# HV_BUCK.net
KiCad netlist of a schematic drawn in Altium Designer
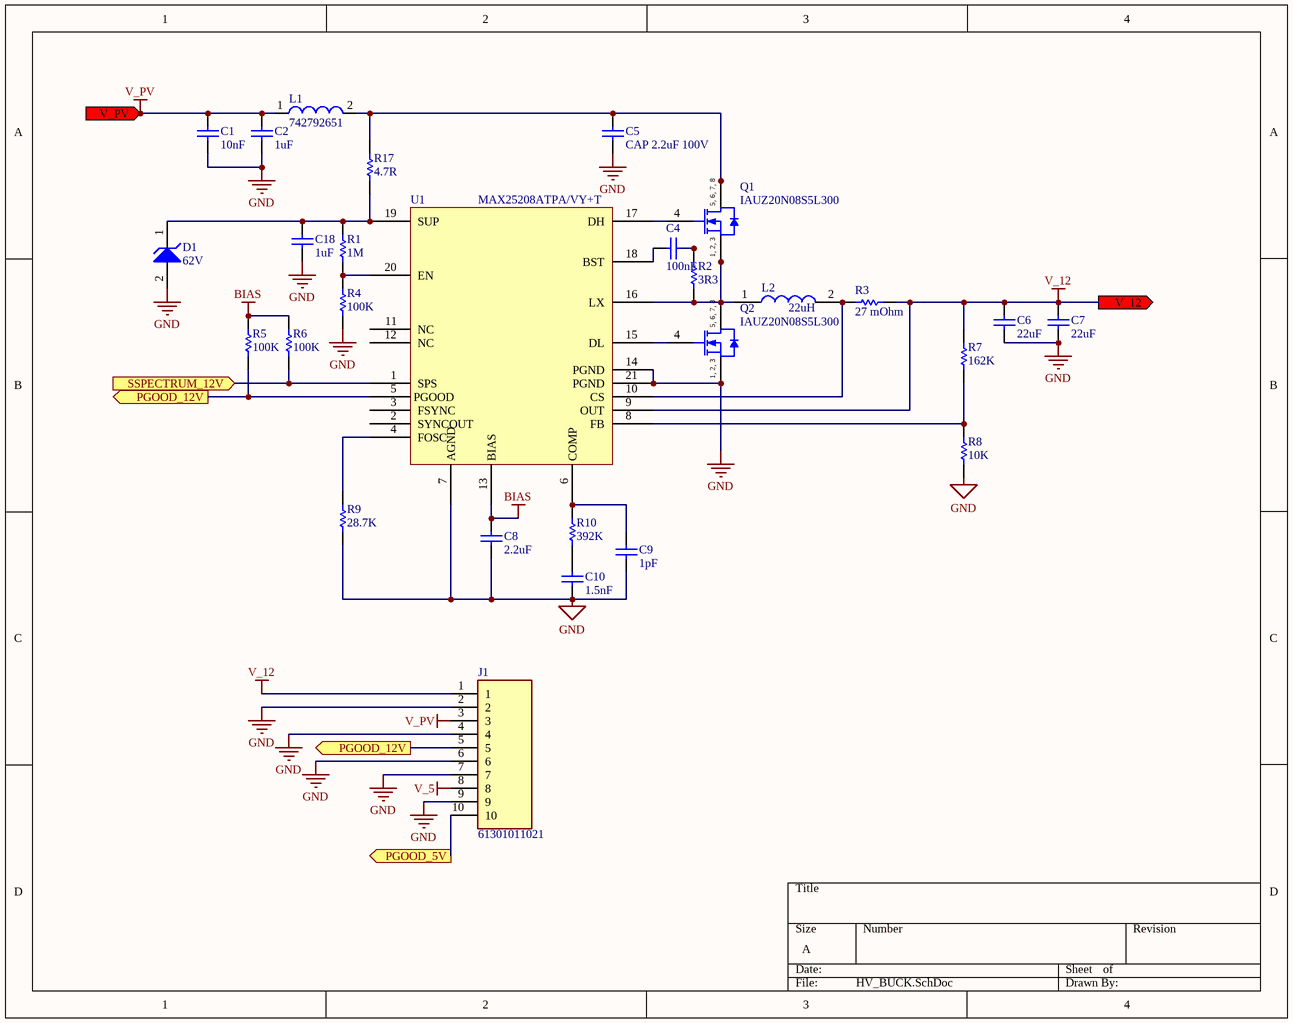
[diagram p0: HV_BUCK.SchDoc]

(export (version "E")
  (design (tool "Eeschema 10.0.6"))
  (components
    (comp (ref "C1")
      (value "10nF")
      (footprint "CAPC2013X94X50ML20T25")
      (description "Cap Ceramic 0.01uF 100V X7R 10% SMD 0805 FlexiTerm 125C Paper T/R")
      (fields
        (field (name "MANUFACTURER") "AVX Interconnect / Elco")
        (field (name "PART NUMBER") "08051C103KAZ2A")
      )
      (libsource (lib "Altium Content Vault") (part "CAP"))
    )
    (comp (ref "C2")
      (value "1uF")
      (footprint "CAPC3216X180X50NL20T25")
      (description "Chip Capacitor, 1 uF, +/- 10%, 100 V, -55 to 125 degC, 1206 (3216 Metric), RoHS, Tape and Reel")
      (fields (field (name "MANUFACTURER") "AVX"))
      (libsource (lib "Altium Content Vault") (part "CAP-NP-2"))
    )
    (comp (ref "C4")
      (value "100nF")
      (footprint "CAPC1005X56X25NL10T15")
      (fields
        (field (name "MANUFACTURER") "AVX Interconnect / Elco")
        (field (name "PART NUMBER") "0402YC104KAT2A")
        (field (name "TOLERANCE") "10%")
      )
      (libsource (lib "Altium Content Vault") (part "CAP"))
    )
    (comp (ref "C5")
      (value "CAP 2.2uF 100V")
      (footprint "CAPC1210(3225)280_N")
      (description "CAP 2.2uF 100V ±10% 1210 (3225 Metric) Thickness 2.8mm SMD")
      (fields (field (name "TOLERANCE") "Â±10%"))
      (libsource (lib "Altium Content Vault") (part "CAP"))
    )
    (comp (ref "C6")
      (value "22uF")
      (footprint "CAPC3225X279X50NL20T25")
      (description "Ceramic Capacitor, 25 V, 22 uF, +/-10%, -55 to 85 degC, 2-Pin SMD (1210), RoHS, Tape and Reel")
      (fields (field (name "TOLERANCE") "10%") (field (name "MANUFACTURER") "AVX"))
      (libsource (lib "Altium Content Vault") (part "CAP-NP-2"))
    )
    (comp (ref "C7")
      (value "22uF")
      (footprint "CAPC3225X279X50NL20T25")
      (description "Ceramic Capacitor, 25 V, 22 uF, +/-10%, -55 to 85 degC, 2-Pin SMD (1210), RoHS, Tape and Reel")
      (fields (field (name "TOLERANCE") "10%") (field (name "MANUFACTURER") "AVX"))
      (libsource (lib "Altium Content Vault") (part "CAP-NP-2"))
    )
    (comp (ref "C8")
      (value "2.2uF")
      (footprint "CAPC2013X135X50ML10T20")
      (fields
        (field (name "MANUFACTURER") "Murata")
        (field (name "PART NUMBER") "GRM21BR71C225KA12L")
        (field (name "TOLERANCE") "10%")
      )
      (libsource (lib "Altium Content Vault") (part "CAP"))
    )
    (comp (ref "C9")
      (value "1pF")
      (footprint "CAPC1005X55X25NL05T05")
      (description "Chip Capacitor, 1 pF, +/- 0.25 pF, 50 V, -55 to 125 degC, 0402 (1005 Metric), RoHS, Tape and Reel")
      (fields (field (name "TOLERANCE") "5%") (field (name "MANUFACTURER") "Yageo"))
      (libsource (lib "Altium Content Vault") (part "CAP-NP-2"))
    )
    (comp (ref "C10")
      (value "1.5nF")
      (footprint "CAPC1005X55X25ML05T10")
      (fields
        (field (name "PART NUMBER") "GRM155R71H152KA01D")
        (field (name "MANUFACTURER") "Murata")
        (field (name "TOLERANCE") "10%")
      )
      (libsource (lib "Altium Content Vault") (part "CAP"))
    )
    (comp (ref "C18")
      (value "1uF")
      (footprint "CAPC2013X145X20NL20")
      (description "Chip Capacitor, 1 uF, +/- 10%, 100 V, -55 to 125 degC, 0805 (2012 Metric), RoHS, Tape and Reel")
      (fields
        (field (name "PCN PART NUMBER") "MLCCPartNumberChange30/Nov/2012")
        (field (name "MANUFACTURER") "TDK")
      )
      (libsource (lib "Altium Content Vault") (part "CAP-NP-2"))
    )
    (comp (ref "D1")
      (value "62V")
      (footprint "ONSC-SOD-123-2-425-04_V")
      (description "Zener Voltage Regulator, 500 mW, 2-Pin SOD-123, Pb-Free, Tape and Reel")
      (fields (field (name "MANUFACTURER") "On Semiconductor") (field (name "PARTNUMBER") "SZMMSZ5265BT1G"))
      (libsource (lib "Altium Content Vault") (part "ONSC-K1A2-2"))
    )
    (comp (ref "J1")
      (value "61301011021")
      (footprint "SamacSys:HDRRA10W64P0X254_1X10_2540X254X254P")
      (description "Connector")
      (fields (field (name "MOUSER PART NUMBER") "710-61301011021"))
      (libsource (lib "*") (part "61301011021"))
    )
    (comp (ref "L1")
      (value "742792651")
      (footprint "SMD-0603")
      (description "SMD EMI Suppression Ferrite Bead WE-CBF, Z = 600 Ohm")
      (fields (field (name "MANUFACTURER") "Wurth Electronics") (field (name "TOLERANCE") "25%"))
      (libsource (lib "Altium Content Vault") (part "PAS-IND-INDUCTOR-2"))
    )
    (comp (ref "L2")
      (value "22uH")
      (footprint "SamacSys:INDPM8680X400N")
      (description "Inductor 22uH")
      (fields
        (field (name "MANUFACTURER_PART_NUMBER") "MPX1D0840L220")
        (field (name "MOUSER PART NUMBER") "80-MPX1D0840L220")
      )
      (libsource (lib "*") (part "MPX1D0840L470"))
    )
    (comp (ref "Q1")
      (value "IAUZ20N08S5L300")
      (footprint "INF-PG-TSDSON-8-1_V")
      (fields (field (name "MANUFACTURER") "Infineon"))
      (libsource (lib "Altium Content Vault") (part "INF-NEMOS-SSSGDDDD-8"))
    )
    (comp (ref "Q2")
      (value "IAUZ20N08S5L300")
      (footprint "INF-PG-TSDSON-8-1_V")
      (fields (field (name "MANUFACTURER") "Infineon"))
      (libsource (lib "Altium Content Vault") (part "INF-NEMOS-SSSGDDDD-8"))
    )
    (comp (ref "R1")
      (value "1M")
      (footprint "RESC1608X55X25NL10T15")
      (description "RES SMD 1M OHM 1% 1/10W 0603")
      (fields (field (name "MANUFACTURER") "Yageo") (field (name "PART NUMBER") "AC0603FR-071ML"))
      (libsource (lib "Altium Content Vault") (part "RES"))
    )
    (comp (ref "R2")
      (value "3R3")
      (footprint "RESC1005X40X25NL05T10")
      (description "Res Thick Film 0402 3.3 Ohm 1% 1/16W ±200ppm/°C Molded SMD Paper T/R")
      (fields (field (name "MANUFACTURER") "Yageo / Phycomp") (field (name "PART NUMBER") "RC0402FR-073R3L"))
      (libsource (lib "Altium Content Vault") (part "RES"))
    )
    (comp (ref "R3")
      (value "27 mOhm")
      (footprint "RESC3116X65X40NL10T20")
      (fields
        (field (name "MANUFACTURER") "Yageo")
        (field (name "PART NUMBER") "RL1206FR-070R027L")
        (field (name "TOLERANCE") "1%")
      )
      (libsource (lib "Altium Content Vault") (part "RES"))
    )
    (comp (ref "R4")
      (value "100K")
      (footprint "RESC1608X55X25NL10T15")
      (description "Chip Resistor, 100 KOhm, +/- 1%, 0.1 W, -55 to 155 degC, 0603 (1608 Metric), RoHS, Tape and Reel")
      (fields (field (name "MANUFACTURER") "Yageo") (field (name "TOLERANCE") "1%"))
      (libsource (lib "Altium Content Vault") (part "RES-2"))
    )
    (comp (ref "R5")
      (value "100K")
      (footprint "RESC1005X40X25NL05T10")
      (description "Res General Purpose Thick Film 0402 100K Ohm 1% 1/16W ±100ppm/°C Molded SMD Paper T/R")
      (fields (field (name "PART NUMBER") "RC0402FR-07100KL") (field (name "MANUFACTURER") "Yageo / Phycomp"))
      (libsource (lib "Altium Content Vault") (part "RES"))
    )
    (comp (ref "R6")
      (value "100K")
      (footprint "RESC1005X40X25NL05T10")
      (description "Res General Purpose Thick Film 0402 100K Ohm 1% 1/16W ±100ppm/°C Molded SMD Paper T/R")
      (fields (field (name "PART NUMBER") "RC0402FR-07100KL") (field (name "MANUFACTURER") "Yageo / Phycomp"))
      (libsource (lib "Altium Content Vault") (part "RES"))
    )
    (comp (ref "R7")
      (value "162K")
      (footprint "RESC1005X40X25NL05T10")
      (fields
        (field (name "PART NUMBER") "RC0402FR-07162KL")
        (field (name "MANUFACTURER") "Yageo / Phycomp")
        (field (name "TOLERANCE") "1%")
      )
      (libsource (lib "Altium Content Vault") (part "RES"))
    )
    (comp (ref "R8")
      (value "10K")
      (footprint "RESC1005X40X25NL05T10")
      (fields
        (field (name "PART NUMBER") "RC0402FR-0710KL")
        (field (name "MANUFACTURER") "Yageo / Phycomp")
        (field (name "TOLERANCE") "1%")
      )
      (libsource (lib "Altium Content Vault") (part "RES"))
    )
    (comp (ref "R9")
      (value "28.7K")
      (footprint "RESC1005X40X25NL05T05")
      (description "RES SMD 28.7K OHM 1% 1/10W 0402")
      (fields (field (name "PART NUMBER") "ERJ-2RKF2872X") (field (name "MANUFACTURER") "Panasonic"))
      (libsource (lib "Altium Content Vault") (part "RES"))
    )
    (comp (ref "R10")
      (value "392K")
      (footprint "RESC1005X40X25NL05T10")
      (description "Res Thick Film 0402 392K Ohm 1% 1/16W 100ppm/C Molded SMD Paper T/R")
      (fields (field (name "MANUFACTURER") "Yageo") (field (name "PART NUMBER") "RC0402FR07392KL"))
      (libsource (lib "Altium Content Vault") (part "RES"))
    )
    (comp (ref "R17")
      (value "4.7R")
      (footprint "RESC2013X70X40NL20T20")
      (description "Chip Resistor, 4.7 Ohm, +/- 1%, 125 mW, -55 to 125 degC, 0805 (2012 Metric), RoHS, Tape and Reel")
      (fields (field (name "TOLERANCE") "1%") (field (name "PARTNUMBER") "ERJ-6RQF4R7V"))
      (libsource (lib "Altium Content Vault") (part "RES-2"))
    )
    (comp (ref "U1")
      (value "MAX25208")
      (footprint "QFN50P400X400X80_HS-21N")
      (fields
        (field (name "MANUFACTURER") "Maxim Integrated")
        (field (name "MANUFACTURER PART NUMBER") "MAX25208ATPA/VY+T")
        (field (name "SUPPLIER PART NUMBER 1") "MAX25208ATPA/VY+T")
      )
      (libsource (lib "MAX25208") (part "MAX25208"))
    )
  )
  (nets
    (net (code "1") (name "/PGOOD_5V") (class "Default")
      (node (ref "J1") (pin "10") (pinfunction "10_10") (pintype "passive"))
    )
    (net (code "2") (name "/PGOOD_12V") (class "Default")
      (node (ref "J1") (pin "5") (pinfunction "5_5") (pintype "passive"))
      (node (ref "R5") (pin "2") (pinfunction "2_2") (pintype "passive"))
      (node (ref "U1") (pin "5") (pinfunction "PGOOD_5") (pintype "passive"))
    )
    (net (code "3") (name "/SSPECTRUM_12V") (class "Default")
      (node (ref "R6") (pin "2") (pinfunction "2_2") (pintype "passive"))
      (node (ref "U1") (pin "1") (pinfunction "SPS_1") (pintype "passive"))
    )
    (net (code "4") (name "BIAS") (class "Default")
      (node (ref "C8") (pin "2") (pinfunction "2_2") (pintype "passive"))
      (node (ref "R5") (pin "1") (pinfunction "1_1") (pintype "passive"))
      (node (ref "R6") (pin "1") (pinfunction "1_1") (pintype "passive"))
      (node (ref "U1") (pin "13") (pinfunction "BIAS_13") (pintype "passive"))
    )
    (net (code "5") (name "GND") (class "Default")
      (node (ref "C1") (pin "1") (pinfunction "1_1") (pintype "passive"))
      (node (ref "C10") (pin "1") (pinfunction "1_1") (pintype "passive"))
      (node (ref "C18") (pin "1") (pinfunction "1_1") (pintype "passive"))
      (node (ref "C2") (pin "1") (pinfunction "1_1") (pintype "passive"))
      (node (ref "C5") (pin "1") (pinfunction "1_1") (pintype "passive"))
      (node (ref "C6") (pin "1") (pinfunction "1_1") (pintype "passive"))
      (node (ref "C7") (pin "1") (pinfunction "1_1") (pintype "passive"))
      (node (ref "C8") (pin "1") (pinfunction "1_1") (pintype "passive"))
      (node (ref "C9") (pin "1") (pinfunction "1_1") (pintype "passive"))
      (node (ref "D1") (pin "2") (pinfunction "A_2") (pintype "passive"))
      (node (ref "J1") (pin "2") (pinfunction "2_2") (pintype "passive"))
      (node (ref "J1") (pin "4") (pinfunction "4_4") (pintype "passive"))
      (node (ref "J1") (pin "6") (pinfunction "6_6") (pintype "passive"))
      (node (ref "J1") (pin "7") (pinfunction "7_7") (pintype "passive"))
      (node (ref "J1") (pin "9") (pinfunction "9_9") (pintype "passive"))
      (node (ref "Q2") (pin "1") (pinfunction "SOURCE_1") (pintype "passive"))
      (node (ref "Q2") (pin "2") (pinfunction "SOURCE_2") (pintype "passive"))
      (node (ref "Q2") (pin "3") (pinfunction "SOURCE_3") (pintype "passive"))
      (node (ref "R4") (pin "1") (pinfunction "1_1") (pintype "passive"))
      (node (ref "R8") (pin "1") (pinfunction "1_1") (pintype "passive"))
      (node (ref "R9") (pin "1") (pinfunction "1_1") (pintype "passive"))
      (node (ref "U1") (pin "14") (pinfunction "PGND_14") (pintype "passive"))
      (node (ref "U1") (pin "21") (pinfunction "PGND_21") (pintype "passive"))
      (node (ref "U1") (pin "7") (pinfunction "AGND_7") (pintype "passive"))
    )
    (net (code "6") (name "Net-(C4-Pad2)") (class "Default")
      (node (ref "C4") (pin "2") (pinfunction "2_2") (pintype "passive"))
      (node (ref "R2") (pin "2") (pinfunction "2_2") (pintype "passive"))
    )
    (net (code "7") (name "Net-(C5-Pad2)") (class "Default")
      (node (ref "C5") (pin "2") (pinfunction "2_2") (pintype "passive"))
      (node (ref "L1") (pin "2") (pinfunction "2_2") (pintype "passive"))
      (node (ref "Q1") (pin "5") (pinfunction "DRAIN_5") (pintype "passive"))
      (node (ref "Q1") (pin "6") (pinfunction "DRAIN_6") (pintype "passive"))
      (node (ref "Q1") (pin "7") (pinfunction "DRAIN_7") (pintype "passive"))
      (node (ref "Q1") (pin "8") (pinfunction "DRAIN_8") (pintype "passive"))
      (node (ref "R17") (pin "2") (pinfunction "2_2") (pintype "passive"))
    )
    (net (code "8") (name "Net-(C10-Pad2)") (class "Default")
      (node (ref "C10") (pin "2") (pinfunction "2_2") (pintype "passive"))
      (node (ref "R10") (pin "1") (pinfunction "1_1") (pintype "passive"))
    )
    (net (code "9") (name "Net-(D1-K)") (class "Default")
      (node (ref "C18") (pin "2") (pinfunction "2_2") (pintype "passive"))
      (node (ref "D1") (pin "1") (pinfunction "K_1") (pintype "passive"))
      (node (ref "R1") (pin "2") (pinfunction "2_2") (pintype "passive"))
      (node (ref "R17") (pin "1") (pinfunction "1_1") (pintype "passive"))
      (node (ref "U1") (pin "19") (pinfunction "SUP_19") (pintype "passive"))
    )
    (net (code "10") (name "Net-(Q1-GATE)") (class "Default")
      (node (ref "Q1") (pin "4") (pinfunction "GATE_4") (pintype "passive"))
      (node (ref "U1") (pin "17") (pinfunction "DH_17") (pintype "passive"))
    )
    (net (code "11") (name "Net-(Q2-GATE)") (class "Default")
      (node (ref "Q2") (pin "4") (pinfunction "GATE_4") (pintype "passive"))
      (node (ref "U1") (pin "15") (pinfunction "DL_15") (pintype "passive"))
    )
    (net (code "12") (name "Net-(U1-BST)") (class "Default")
      (node (ref "C4") (pin "1") (pinfunction "1_1") (pintype "passive"))
      (node (ref "U1") (pin "18") (pinfunction "BST_18") (pintype "passive"))
    )
    (net (code "13") (name "Net-(U1-COMP)") (class "Default")
      (node (ref "C9") (pin "2") (pinfunction "2_2") (pintype "passive"))
      (node (ref "R10") (pin "2") (pinfunction "2_2") (pintype "passive"))
      (node (ref "U1") (pin "6") (pinfunction "COMP_6") (pintype "passive"))
    )
    (net (code "14") (name "Net-(U1-CS)") (class "Default")
      (node (ref "L2") (pin "2") (pinfunction "2_2") (pintype "passive"))
      (node (ref "R3") (pin "1") (pinfunction "1_1") (pintype "passive"))
      (node (ref "U1") (pin "10") (pinfunction "CS_10") (pintype "passive"))
    )
    (net (code "15") (name "Net-(U1-EN)") (class "Default")
      (node (ref "R1") (pin "1") (pinfunction "1_1") (pintype "passive"))
      (node (ref "R4") (pin "2") (pinfunction "2_2") (pintype "passive"))
      (node (ref "U1") (pin "20") (pinfunction "EN_20") (pintype "passive"))
    )
    (net (code "16") (name "Net-(U1-FB)") (class "Default")
      (node (ref "R7") (pin "1") (pinfunction "1_1") (pintype "passive"))
      (node (ref "R8") (pin "2") (pinfunction "2_2") (pintype "passive"))
      (node (ref "U1") (pin "8") (pinfunction "FB_8") (pintype "passive"))
    )
    (net (code "17") (name "Net-(U1-FOSC)") (class "Default")
      (node (ref "R9") (pin "2") (pinfunction "2_2") (pintype "passive"))
      (node (ref "U1") (pin "4") (pinfunction "FOSC_4") (pintype "passive"))
    )
    (net (code "18") (name "Net-(U1-LX)") (class "Default")
      (node (ref "L2") (pin "1") (pinfunction "1_1") (pintype "passive"))
      (node (ref "Q1") (pin "1") (pinfunction "SOURCE_1") (pintype "passive"))
      (node (ref "Q1") (pin "2") (pinfunction "SOURCE_2") (pintype "passive"))
      (node (ref "Q1") (pin "3") (pinfunction "SOURCE_3") (pintype "passive"))
      (node (ref "Q2") (pin "5") (pinfunction "DRAIN_5") (pintype "passive"))
      (node (ref "Q2") (pin "6") (pinfunction "DRAIN_6") (pintype "passive"))
      (node (ref "Q2") (pin "7") (pinfunction "DRAIN_7") (pintype "passive"))
      (node (ref "Q2") (pin "8") (pinfunction "DRAIN_8") (pintype "passive"))
      (node (ref "R2") (pin "1") (pinfunction "1_1") (pintype "passive"))
      (node (ref "U1") (pin "16") (pinfunction "LX_16") (pintype "passive"))
    )
    (net (code "19") (name "V_5") (class "Default")
      (node (ref "J1") (pin "8") (pinfunction "8_8") (pintype "passive"))
    )
    (net (code "20") (name "V_12") (class "Default")
      (node (ref "C6") (pin "2") (pinfunction "2_2") (pintype "passive"))
      (node (ref "C7") (pin "2") (pinfunction "2_2") (pintype "passive"))
      (node (ref "J1") (pin "1") (pinfunction "1_1") (pintype "passive"))
      (node (ref "R3") (pin "2") (pinfunction "2_2") (pintype "passive"))
      (node (ref "R7") (pin "2") (pinfunction "2_2") (pintype "passive"))
      (node (ref "U1") (pin "9") (pinfunction "OUT_9") (pintype "passive"))
    )
    (net (code "21") (name "V_PV") (class "Default")
      (node (ref "C1") (pin "2") (pinfunction "2_2") (pintype "passive"))
      (node (ref "C2") (pin "2") (pinfunction "2_2") (pintype "passive"))
      (node (ref "J1") (pin "3") (pinfunction "3_3") (pintype "passive"))
      (node (ref "L1") (pin "1") (pinfunction "1_1") (pintype "passive"))
    )
    (net (code "22") (name "unconnected-(U1-FSYNC-Pad3)") (class "Default")
      (node (ref "U1") (pin "3") (pinfunction "FSYNC_3") (pintype "passive"))
    )
    (net (code "23") (name "unconnected-(U1-NC-Pad11)") (class "Default")
      (node (ref "U1") (pin "11") (pinfunction "NC_11") (pintype "passive"))
    )
    (net (code "24") (name "unconnected-(U1-NC-Pad12)") (class "Default")
      (node (ref "U1") (pin "12") (pinfunction "NC_12") (pintype "passive"))
    )
    (net (code "25") (name "unconnected-(U1-SYNCOUT-Pad2)") (class "Default")
      (node (ref "U1") (pin "2") (pinfunction "SYNCOUT_2") (pintype "passive"))
    )
  )
)
